# main.net
KiCad netlist of a schematic drawn in Altium Designer
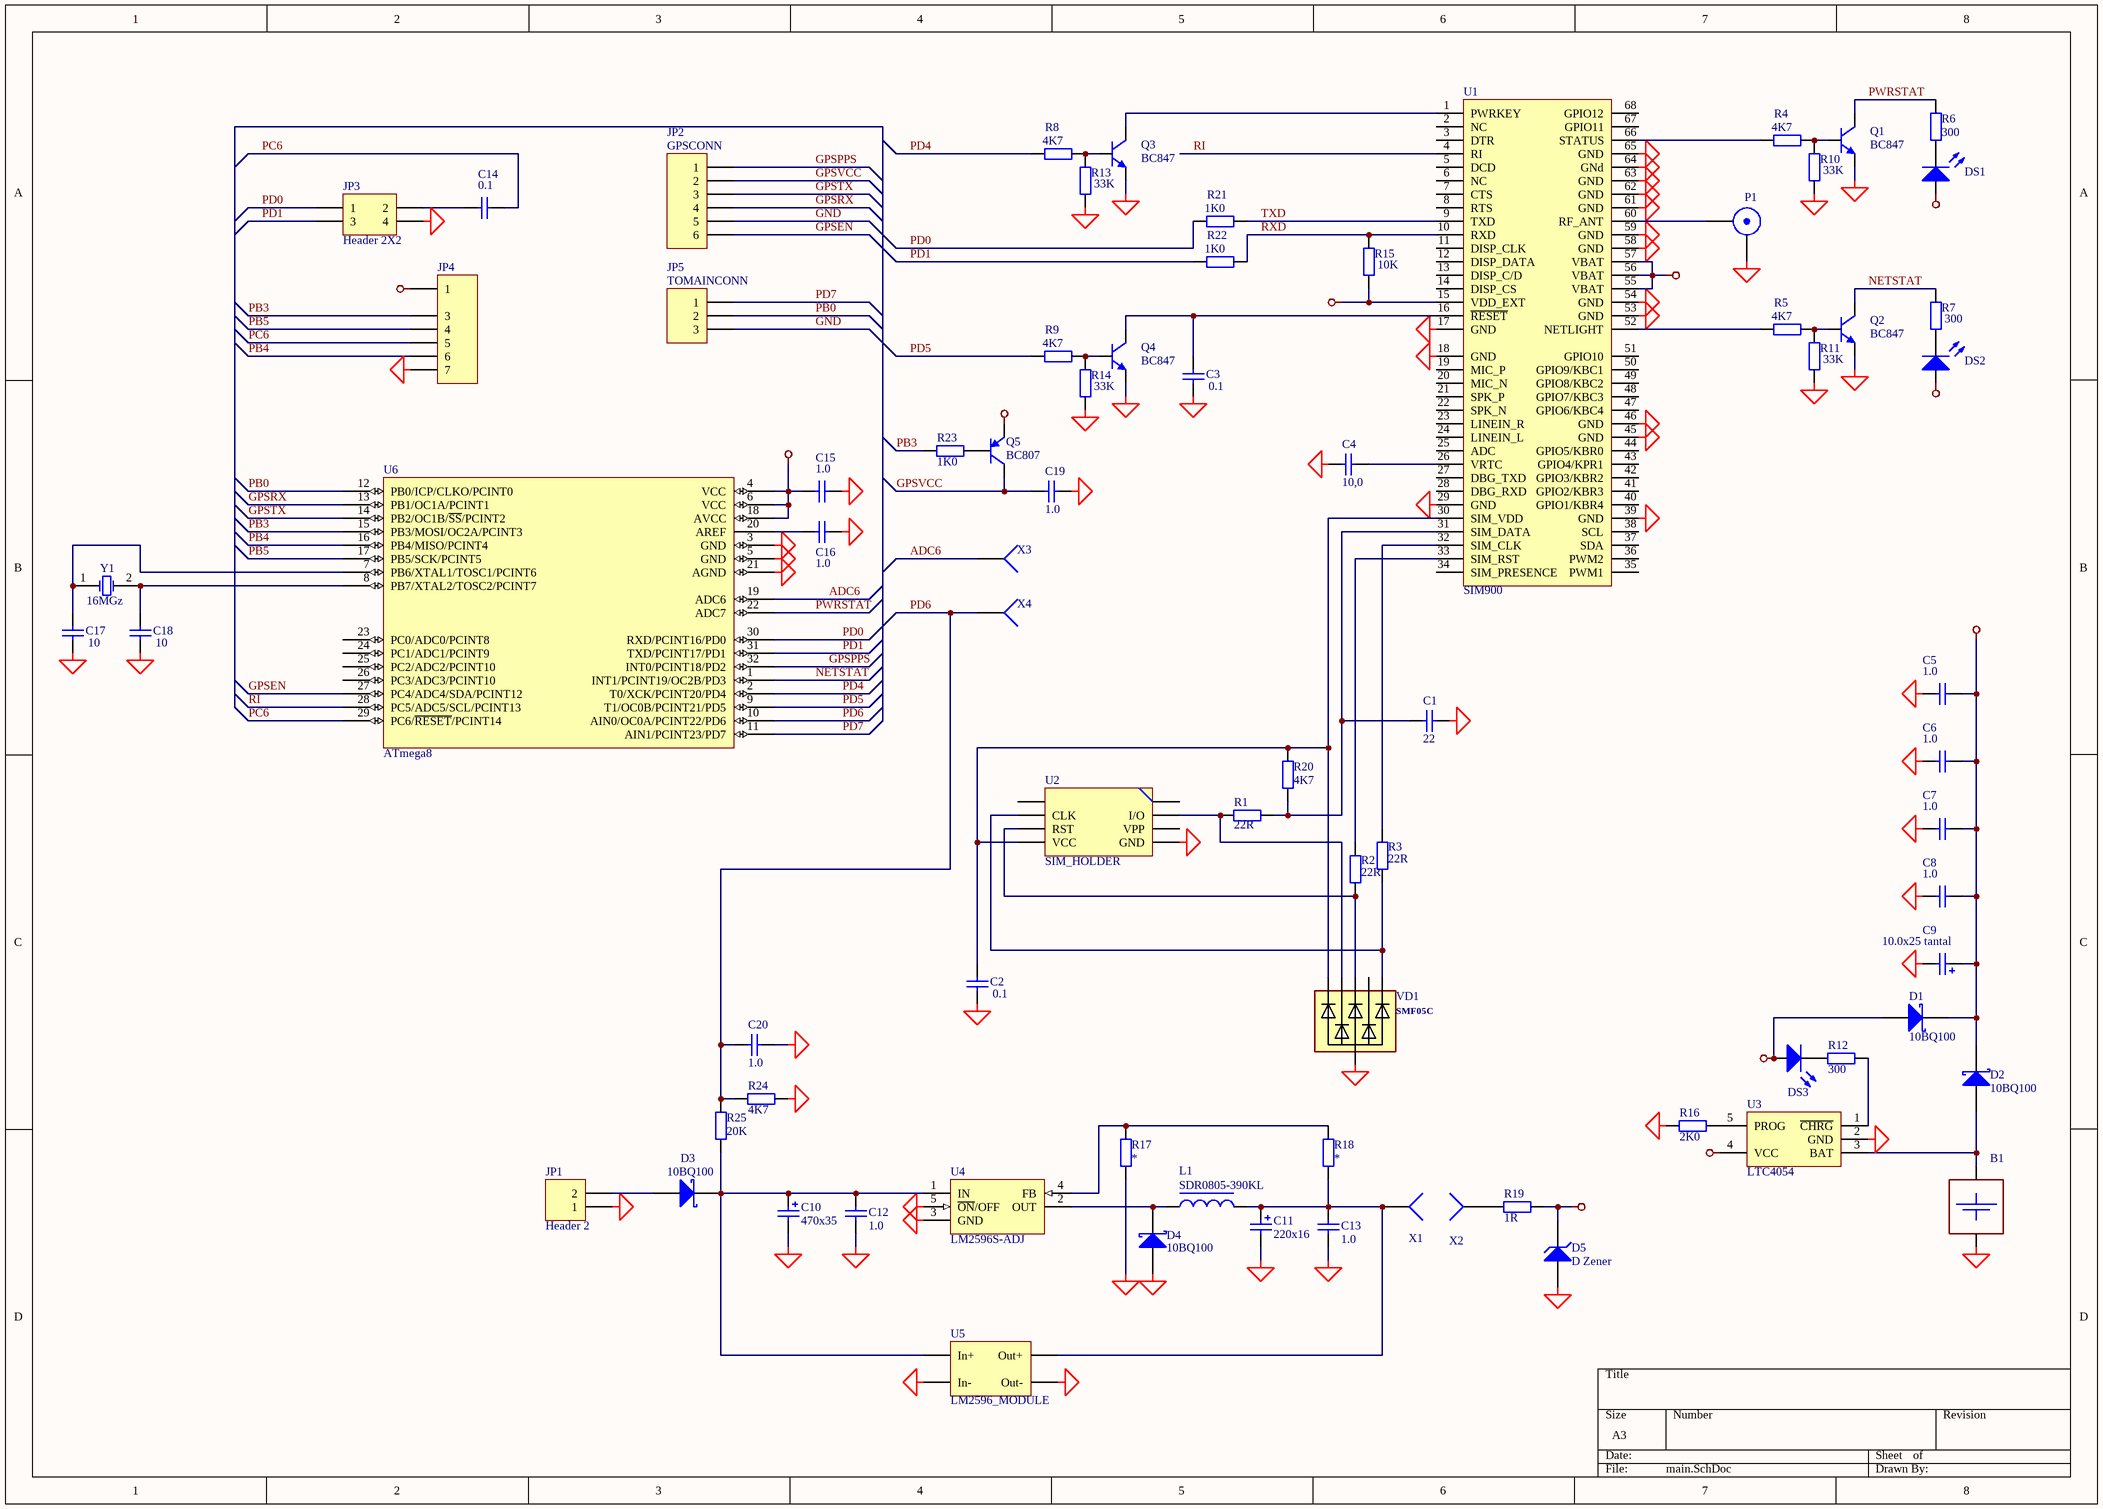
[diagram p0: main.SchDoc]

(export (version "E")
  (design (tool "Eeschema 10.0.6"))
  (components
    (comp (ref "B1")
      (value "BAT18650_HOLDER")
      (footprint "BAT18650_HOLDER")
      (libsource (lib "PAL") (part "BAT18650_HOLDER"))
    )
    (comp (ref "C1")
      (value "22")
      (footprint "_1206")
      (description "Capacitor")
      (fields (field (name "MANUFACTURER") "Generic Components") (field (name "PUBLISHER") "Altium Limited"))
      (libsource (lib "Miscellaneous Devices") (part "Cap Semi"))
    )
    (comp (ref "C2")
      (value "0.1")
      (footprint "_1206")
      (description "Capacitor")
      (fields (field (name "MANUFACTURER") "Generic Components") (field (name "PUBLISHER") "Altium Limited"))
      (libsource (lib "Miscellaneous Devices") (part "Cap Semi"))
    )
    (comp (ref "C3")
      (value "0.1")
      (footprint "_1206")
      (description "Capacitor")
      (fields (field (name "MANUFACTURER") "Generic Components") (field (name "PUBLISHER") "Altium Limited"))
      (libsource (lib "Miscellaneous Devices") (part "Cap Semi"))
    )
    (comp (ref "C4")
      (value "10,0")
      (footprint "_1206")
      (description "Capacitor")
      (fields (field (name "MANUFACTURER") "Generic Components") (field (name "PUBLISHER") "Altium Limited"))
      (libsource (lib "Miscellaneous Devices") (part "Cap Semi"))
    )
    (comp (ref "C5")
      (value "1.0")
      (footprint "_1206")
      (description "Capacitor")
      (fields (field (name "MANUFACTURER") "Generic Components") (field (name "PUBLISHER") "Altium Limited"))
      (libsource (lib "Miscellaneous Devices") (part "Cap Semi"))
    )
    (comp (ref "C6")
      (value "1.0")
      (footprint "_1206")
      (description "Capacitor")
      (fields (field (name "MANUFACTURER") "Generic Components") (field (name "PUBLISHER") "Altium Limited"))
      (libsource (lib "Miscellaneous Devices") (part "Cap Semi"))
    )
    (comp (ref "C7")
      (value "1.0")
      (footprint "_1206")
      (description "Capacitor")
      (fields (field (name "MANUFACTURER") "Generic Components") (field (name "PUBLISHER") "Altium Limited"))
      (libsource (lib "Miscellaneous Devices") (part "Cap Semi"))
    )
    (comp (ref "C8")
      (value "1.0")
      (footprint "_1206")
      (description "Capacitor")
      (fields (field (name "MANUFACTURER") "Generic Components") (field (name "PUBLISHER") "Altium Limited"))
      (libsource (lib "Miscellaneous Devices") (part "Cap Semi"))
    )
    (comp (ref "C9")
      (value "10.0x25 tantal")
      (footprint "CAP_EL_6_3")
      (description "Polarized Capacitor (Radial)")
      (fields (field (name "MANUFACTURER") "Generic Components") (field (name "PUBLISHER") "Altium Limited"))
      (libsource (lib "PAL") (part "Cap Pol1"))
    )
    (comp (ref "C10")
      (value "470x35")
      (footprint "el5")
      (description "Polarized Capacitor (Radial)")
      (fields (field (name "MANUFACTURER") "Generic Components") (field (name "PUBLISHER") "Altium Limited"))
      (libsource (lib "BUF") (part "Cap Pol"))
    )
    (comp (ref "C11")
      (value "220x16")
      (footprint "el3")
      (description "Polarized Capacitor (Radial)")
      (fields (field (name "MANUFACTURER") "Generic Components") (field (name "PUBLISHER") "Altium Limited"))
      (libsource (lib "BUF") (part "Cap Pol"))
    )
    (comp (ref "C12")
      (value "Cap")
      (footprint "_1206")
      (description "Capacitor")
      (fields
        (field (name "MANUFACTURER") "Generic Components")
        (field (name "ALTIUM_VALUE") "1.0")
        (field (name "PUBLISHER") "Altium Limited")
      )
      (libsource (lib "BUF") (part "Cap"))
    )
    (comp (ref "C13")
      (value "Cap")
      (footprint "_1206")
      (description "Capacitor")
      (fields
        (field (name "MANUFACTURER") "Generic Components")
        (field (name "ALTIUM_VALUE") "1.0")
        (field (name "PUBLISHER") "Altium Limited")
      )
      (libsource (lib "BUF") (part "Cap"))
    )
    (comp (ref "C14")
      (value "0.1")
      (footprint "_1206")
      (description "Capacitor")
      (fields (field (name "MANUFACTURER") "Generic Components") (field (name "PUBLISHER") "Altium Limited"))
      (libsource (lib "Miscellaneous Devices") (part "Cap Semi"))
    )
    (comp (ref "C15")
      (value "1.0")
      (footprint "_1206")
      (description "Capacitor")
      (fields (field (name "MANUFACTURER") "Generic Components") (field (name "PUBLISHER") "Altium Limited"))
      (libsource (lib "Miscellaneous Devices") (part "Cap Semi"))
    )
    (comp (ref "C16")
      (value "1.0")
      (footprint "_1206")
      (description "Capacitor")
      (fields (field (name "MANUFACTURER") "Generic Components") (field (name "PUBLISHER") "Altium Limited"))
      (libsource (lib "Miscellaneous Devices") (part "Cap Semi"))
    )
    (comp (ref "C17")
      (value "10")
      (footprint "_1206")
      (description "Capacitor")
      (fields (field (name "MANUFACTURER") "Generic Components") (field (name "PUBLISHER") "Altium Limited"))
      (libsource (lib "Miscellaneous Devices") (part "Cap Semi"))
    )
    (comp (ref "C18")
      (value "10")
      (footprint "_1206")
      (description "Capacitor")
      (fields (field (name "MANUFACTURER") "Generic Components") (field (name "PUBLISHER") "Altium Limited"))
      (libsource (lib "Miscellaneous Devices") (part "Cap Semi"))
    )
    (comp (ref "C19")
      (value "1.0")
      (footprint "_1206")
      (description "Capacitor")
      (fields (field (name "MANUFACTURER") "Generic Components") (field (name "PUBLISHER") "Altium Limited"))
      (libsource (lib "Miscellaneous Devices") (part "Cap Semi"))
    )
    (comp (ref "C20")
      (value "Cap")
      (footprint "_1206")
      (description "Capacitor")
      (fields
        (field (name "MANUFACTURER") "Generic Components")
        (field (name "ALTIUM_VALUE") "1.0")
        (field (name "PUBLISHER") "Altium Limited")
      )
      (libsource (lib "BUF") (part "Cap"))
    )
    (comp (ref "D1")
      (value "10BQ100")
      (footprint "DSO-C2/X2.3")
      (description "Schottky Rectifier")
      (fields
        (field (name "MANUFACTURER") "International Rectifier")
        (field (name "PUBLISHER") "Altium Limited")
      )
      (libsource (lib "IR Discrete Diode") (part "10BQ015"))
    )
    (comp (ref "D2")
      (value "10BQ100")
      (footprint "DSO-C2/X2.3")
      (description "Schottky Rectifier")
      (fields
        (field (name "MANUFACTURER") "International Rectifier")
        (field (name "PUBLISHER") "Altium Limited")
      )
      (libsource (lib "IR Discrete Diode") (part "10BQ015"))
    )
    (comp (ref "D3")
      (value "10BQ100")
      (footprint "DSO-C2/X2.3")
      (description "Schottky Rectifier")
      (fields
        (field (name "MANUFACTURER") "International Rectifier")
        (field (name "PUBLISHER") "Altium Limited")
      )
      (libsource (lib "IR Discrete Diode") (part "10BQ015"))
    )
    (comp (ref "D4")
      (value "10BQ100")
      (footprint "DSO-C2/X2.3")
      (description "Schottky Rectifier")
      (fields
        (field (name "MANUFACTURER") "International Rectifier")
        (field (name "PUBLISHER") "Altium Limited")
      )
      (libsource (lib "IR Discrete Diode") (part "10BQ015"))
    )
    (comp (ref "D5")
      (value "D Zener")
      (footprint "_1206d")
      (description "Zener Diode")
      (fields (field (name "MANUFACTURER") "Generic Components") (field (name "PUBLISHER") "Altium Limited"))
      (libsource (lib "Miscellaneous Devices") (part "D Zener"))
    )
    (comp (ref "DS1")
      (value "LED0")
      (footprint "el3")
      (description "Typical INFRARED GaAs LED")
      (fields (field (name "MANUFACTURER") "Generic Components") (field (name "PUBLISHER") "Altium Limited"))
      (libsource (lib "PAL") (part "LED0"))
    )
    (comp (ref "DS2")
      (value "LED0")
      (footprint "el3")
      (description "Typical INFRARED GaAs LED")
      (fields (field (name "MANUFACTURER") "Generic Components") (field (name "PUBLISHER") "Altium Limited"))
      (libsource (lib "PAL") (part "LED0"))
    )
    (comp (ref "DS3")
      (value "LED0")
      (footprint "el3")
      (description "Typical INFRARED GaAs LED")
      (fields (field (name "MANUFACTURER") "Generic Components") (field (name "PUBLISHER") "Altium Limited"))
      (libsource (lib "") (part "LED0_1"))
    )
    (comp (ref "JP1")
      (value "Header 2")
      (footprint "BT5-2")
      (description "Header, 2-Pin")
      (fields (field (name "MANUFACTURER") "Generic Components") (field (name "PUBLISHER") "Altium Limited"))
      (libsource (lib "BUF") (part "Header 2"))
    )
    (comp (ref "JP2")
      (value "GPSCONN")
      (footprint "HDR1X6")
      (description "Header, 6-Pin")
      (fields (field (name "MANUFACTURER") "Generic Components") (field (name "PUBLISHER") "Altium Limited"))
      (libsource (lib "Miscellaneous Connectors") (part "Header 6"))
    )
    (comp (ref "JP3")
      (value "Header 2X2")
      (footprint "HDR2X2")
      (description "Header, 2-Pin, Dual row")
      (fields (field (name "MANUFACTURER") "Generic Components") (field (name "PUBLISHER") "Altium Limited"))
      (libsource (lib "Miscellaneous Connectors") (part "Header 2X2"))
    )
    (comp (ref "JP4")
      (value "AVR_conn")
      (footprint "AVR_CONN")
      (description "Header, 7-Pin")
      (fields (field (name "MANUFACTURER") "Generic Components") (field (name "PUBLISHER") "Altium Limited"))
      (libsource (lib "PAL") (part "AVR_conn"))
    )
    (comp (ref "JP5")
      (value "TOMAINCONN")
      (footprint "HDR1X3")
      (description "Header, 3-Pin")
      (fields (field (name "MANUFACTURER") "Generic Components") (field (name "PUBLISHER") "Altium Limited"))
      (libsource (lib "Miscellaneous Connectors") (part "Header 3"))
    )
    (comp (ref "L1")
      (value "SDR0805-390KL")
      (footprint "L10x10")
      (description "Magnetic-Core Inductor")
      (fields (field (name "MANUFACTURER") "Generic Components") (field (name "PUBLISHER") "Altium Limited"))
      (libsource (lib "PAL") (part "Inductor Konstr 2"))
    )
    (comp (ref "P1")
      (value "SMB")
      (footprint "SMB_V-RJ45")
      (description "SMB Straight Connector")
      (fields (field (name "MANUFACTURER") "Generic Components") (field (name "PUBLISHER") "Altium Limited"))
      (libsource (lib "Miscellaneous Connectors") (part "SMB"))
    )
    (comp (ref "Q1")
      (value "BC847")
      (footprint "SO-G3/C2.5")
      (description "General Purpose Transistor NPN Silicon")
      (fields (field (name "MANUFACTURER") "Motorola") (field (name "PUBLISHER") "Altium Limited"))
      (libsource (lib "PAL") (part "BC847ALT1"))
    )
    (comp (ref "Q2")
      (value "BC847")
      (footprint "SO-G3/C2.5")
      (description "General Purpose Transistor NPN Silicon")
      (fields (field (name "MANUFACTURER") "Motorola") (field (name "PUBLISHER") "Altium Limited"))
      (libsource (lib "PAL") (part "BC847ALT1"))
    )
    (comp (ref "Q3")
      (value "BC847")
      (footprint "SO-G3/C2.5")
      (description "General Purpose Transistor NPN Silicon")
      (fields (field (name "MANUFACTURER") "Motorola") (field (name "PUBLISHER") "Altium Limited"))
      (libsource (lib "PAL") (part "BC847ALT1"))
    )
    (comp (ref "Q4")
      (value "BC847")
      (footprint "SO-G3/C2.5")
      (description "General Purpose Transistor NPN Silicon")
      (fields (field (name "MANUFACTURER") "Motorola") (field (name "PUBLISHER") "Altium Limited"))
      (libsource (lib "PAL") (part "BC847ALT1"))
    )
    (comp (ref "Q5")
      (value "BC807")
      (footprint "SO-G3/C2.5")
      (description "General Purpose Transistor PNP Silicon")
      (fields (field (name "MANUFACTURER") "Motorola") (field (name "PUBLISHER") "Altium Limited"))
      (libsource (lib "PAL") (part "BC857ALT1"))
    )
    (comp (ref "R1")
      (value "22R")
      (footprint "_1206")
      (description "Resistor")
      (fields (field (name "MANUFACTURER") "Generic Components") (field (name "PUBLISHER") "Altium Limited"))
      (libsource (lib "") (part "Res2_1"))
    )
    (comp (ref "R2")
      (value "22R")
      (footprint "_1206")
      (description "Resistor")
      (fields (field (name "MANUFACTURER") "Generic Components") (field (name "PUBLISHER") "Altium Limited"))
      (libsource (lib "Miscellaneous Devices") (part "Res2"))
    )
    (comp (ref "R3")
      (value "22R")
      (footprint "_1206")
      (description "Resistor")
      (fields (field (name "MANUFACTURER") "Generic Components") (field (name "PUBLISHER") "Altium Limited"))
      (libsource (lib "Miscellaneous Devices") (part "Res2"))
    )
    (comp (ref "R4")
      (value "4K7")
      (footprint "_1206")
      (description "Resistor")
      (fields (field (name "MANUFACTURER") "Generic Components") (field (name "PUBLISHER") "Altium Limited"))
      (libsource (lib "Miscellaneous Devices") (part "Res2"))
    )
    (comp (ref "R5")
      (value "4K7")
      (footprint "_1206")
      (description "Resistor")
      (fields (field (name "MANUFACTURER") "Generic Components") (field (name "PUBLISHER") "Altium Limited"))
      (libsource (lib "Miscellaneous Devices") (part "Res2"))
    )
    (comp (ref "R6")
      (value "300")
      (footprint "_1206")
      (description "Resistor")
      (fields (field (name "MANUFACTURER") "Generic Components") (field (name "PUBLISHER") "Altium Limited"))
      (libsource (lib "") (part "Res2_2"))
    )
    (comp (ref "R7")
      (value "300")
      (footprint "_1206")
      (description "Resistor")
      (fields (field (name "MANUFACTURER") "Generic Components") (field (name "PUBLISHER") "Altium Limited"))
      (libsource (lib "") (part "Res2_1"))
    )
    (comp (ref "R8")
      (value "4K7")
      (footprint "_1206")
      (description "Resistor")
      (fields (field (name "MANUFACTURER") "Generic Components") (field (name "PUBLISHER") "Altium Limited"))
      (libsource (lib "Miscellaneous Devices") (part "Res2"))
    )
    (comp (ref "R9")
      (value "4K7")
      (footprint "_1206")
      (description "Resistor")
      (fields (field (name "MANUFACTURER") "Generic Components") (field (name "PUBLISHER") "Altium Limited"))
      (libsource (lib "Miscellaneous Devices") (part "Res2"))
    )
    (comp (ref "R10")
      (value "33K")
      (footprint "_1206")
      (description "Resistor")
      (fields (field (name "MANUFACTURER") "Generic Components") (field (name "PUBLISHER") "Altium Limited"))
      (libsource (lib "") (part "Res2_1"))
    )
    (comp (ref "R11")
      (value "33K")
      (footprint "_1206")
      (description "Resistor")
      (fields (field (name "MANUFACTURER") "Generic Components") (field (name "PUBLISHER") "Altium Limited"))
      (libsource (lib "") (part "Res2_1"))
    )
    (comp (ref "R12")
      (value "300")
      (footprint "_1206")
      (description "Resistor")
      (fields (field (name "MANUFACTURER") "Generic Components") (field (name "PUBLISHER") "Altium Limited"))
      (libsource (lib "") (part "Res2_3"))
    )
    (comp (ref "R13")
      (value "33K")
      (footprint "_1206")
      (description "Resistor")
      (fields (field (name "MANUFACTURER") "Generic Components") (field (name "PUBLISHER") "Altium Limited"))
      (libsource (lib "") (part "Res2_1"))
    )
    (comp (ref "R14")
      (value "33K")
      (footprint "_1206")
      (description "Resistor")
      (fields (field (name "MANUFACTURER") "Generic Components") (field (name "PUBLISHER") "Altium Limited"))
      (libsource (lib "") (part "Res2_1"))
    )
    (comp (ref "R15")
      (value "10K")
      (footprint "_1206")
      (description "Resistor")
      (fields (field (name "MANUFACTURER") "Generic Components") (field (name "PUBLISHER") "Altium Limited"))
      (libsource (lib "") (part "Res2_1"))
    )
    (comp (ref "R16")
      (value "2K0")
      (footprint "_1206")
      (description "Resistor")
      (fields (field (name "MANUFACTURER") "Generic Components") (field (name "PUBLISHER") "Altium Limited"))
      (libsource (lib "") (part "Res2_3"))
    )
    (comp (ref "R17")
      (value "*")
      (footprint "_1206")
      (description "Resistor")
      (fields (field (name "MANUFACTURER") "Generic Components") (field (name "PUBLISHER") "Altium Limited"))
      (libsource (lib "Miscellaneous Devices") (part "Res2"))
    )
    (comp (ref "R18")
      (value "*")
      (footprint "_1206")
      (description "Resistor")
      (fields (field (name "MANUFACTURER") "Generic Components") (field (name "PUBLISHER") "Altium Limited"))
      (libsource (lib "Miscellaneous Devices") (part "Res2"))
    )
    (comp (ref "R19")
      (value "1R")
      (footprint "_1206")
      (description "Resistor")
      (fields (field (name "MANUFACTURER") "Generic Components") (field (name "PUBLISHER") "Altium Limited"))
      (libsource (lib "") (part "Res2_2"))
    )
    (comp (ref "R20")
      (value "4K7")
      (footprint "_1206")
      (description "Resistor")
      (fields (field (name "MANUFACTURER") "Generic Components") (field (name "PUBLISHER") "Altium Limited"))
      (libsource (lib "Miscellaneous Devices") (part "Res2"))
    )
    (comp (ref "R21")
      (value "1K0")
      (footprint "_1206")
      (description "Resistor")
      (fields (field (name "MANUFACTURER") "Generic Components") (field (name "PUBLISHER") "Altium Limited"))
      (libsource (lib "Miscellaneous Devices") (part "Res2"))
    )
    (comp (ref "R22")
      (value "1K0")
      (footprint "_1206")
      (description "Resistor")
      (fields (field (name "MANUFACTURER") "Generic Components") (field (name "PUBLISHER") "Altium Limited"))
      (libsource (lib "Miscellaneous Devices") (part "Res2"))
    )
    (comp (ref "R23")
      (value "Res2")
      (footprint "_1206")
      (description "Resistor")
      (fields
        (field (name "MANUFACTURER") "Generic Components")
        (field (name "ALTIUM_VALUE") "1K0")
        (field (name "PUBLISHER") "Altium Limited")
      )
      (libsource (lib "Miscellaneous Devices") (part "Res2"))
    )
    (comp (ref "R24")
      (value "4K7")
      (footprint "_1206")
      (description "Resistor")
      (fields (field (name "MANUFACTURER") "Generic Components") (field (name "PUBLISHER") "Altium Limited"))
      (libsource (lib "") (part "Res2_2"))
    )
    (comp (ref "R25")
      (value "20K")
      (footprint "_1206")
      (description "Resistor")
      (fields (field (name "MANUFACTURER") "Generic Components") (field (name "PUBLISHER") "Altium Limited"))
      (libsource (lib "Miscellaneous Devices") (part "Res2"))
    )
    (comp (ref "U1") (value "SIM900") (footprint "SIM900F") (libsource (lib "Schlib1") (part "SIM900")))
    (comp (ref "U2")
      (value "SIM_HOLDER")
      (footprint "SIM_HOLDER_1")
      (libsource (lib "Schlib1") (part "SIM_HOLDER"))
    )
    (comp (ref "U3") (value "LTC4054") (footprint "SO-G5/P.95") (libsource (lib "PAL") (part "LTC4054")))
    (comp (ref "U4")
      (value "LM2596S-ADJ")
      (footprint "SIP-G5/Y2.1")
      (description "Simple Switcher Power Converter 150 kHz 3A Step Down Voltage Regulator")
      (fields
        (field (name "MANUFACTURER") "National Semiconductor")
        (field (name "PUBLISHER") "Altium Limited")
      )
      (libsource (lib "NSC Power Mgt Switching Regulator") (part "LM2596S-ADJ"))
    )
    (comp (ref "U5")
      (value "LM2596_MODULE")
      (footprint "LM2596_MODULE_1")
      (libsource (lib "PAL") (part "LM2596_MODULE"))
    )
    (comp (ref "U6")
      (value "ATmega8")
      (footprint "QFP7X7-G32/X.5N")
      (libsource (lib "PAL") (part "ATmega48/TQFP"))
    )
    (comp (ref "VD1")
      (value "*")
      (footprint "sot363")
      (fields (field (name "MANUFACTURERPARTNUMBER") "SMF05C"))
      (libsource (lib "PAL") (part "SMF05C"))
    )
    (comp (ref "X1")
      (value "Socket")
      (footprint "PIN1")
      (fields (field (name "MANUFACTURER") "Generic Components") (field (name "PUBLISHER") "Altium Limited"))
      (libsource (lib "Miscellaneous Connectors") (part "Socket"))
    )
    (comp (ref "X2")
      (value "Socket")
      (footprint "PIN1")
      (fields (field (name "MANUFACTURER") "Generic Components") (field (name "PUBLISHER") "Altium Limited"))
      (libsource (lib "Miscellaneous Connectors") (part "Socket"))
    )
    (comp (ref "X3")
      (value "Socket")
      (footprint "PIN1")
      (fields (field (name "MANUFACTURER") "Generic Components") (field (name "PUBLISHER") "Altium Limited"))
      (libsource (lib "Miscellaneous Connectors") (part "Socket"))
    )
    (comp (ref "X4")
      (value "Socket")
      (footprint "PIN1")
      (fields (field (name "MANUFACTURER") "Generic Components") (field (name "PUBLISHER") "Altium Limited"))
      (libsource (lib "Miscellaneous Connectors") (part "Socket"))
    )
    (comp (ref "Y1")
      (value "16MGz")
      (footprint "qwarz1")
      (description "Crystal Oscillator")
      (fields (field (name "MANUFACTURER") "Generic Components") (field (name "PUBLISHER") "Altium Limited"))
      (libsource (lib "Miscellaneous Devices") (part "XTAL"))
    )
  )
  (nets
    (net (code "1") (name "+5v") (class "Default")
      (node (ref "D1") (pin "1") (pinfunction "A_1") (pintype "passive"))
      (node (ref "D5") (pin "2") (pinfunction "K_2") (pintype "passive"))
      (node (ref "DS3") (pin "1") (pinfunction "A_1") (pintype "passive"))
      (node (ref "R19") (pin "2") (pinfunction "2_2") (pintype "passive"))
      (node (ref "U3") (pin "4") (pinfunction "VCC_4") (pintype "passive"))
    )
    (net (code "2") (name "/ADC6") (class "Default")
      (node (ref "U6") (pin "19") (pinfunction "ADC6_19") (pintype "bidirectional"))
      (node (ref "X3") (pin "1") (pinfunction "1_1") (pintype "passive"))
    )
    (net (code "3") (name "/GPSEN") (class "Default")
      (node (ref "JP2") (pin "6") (pinfunction "6_6") (pintype "passive"))
      (node (ref "U6") (pin "27") (pinfunction "PC4/ADC4/SDA/PCINT12_27") (pintype "bidirectional"))
    )
    (net (code "4") (name "/GPSPPS") (class "Default")
      (node (ref "JP2") (pin "1") (pinfunction "1_1") (pintype "passive"))
      (node (ref "U6") (pin "32") (pinfunction "INT0/PCINT18/PD2_32") (pintype "bidirectional"))
    )
    (net (code "5") (name "/GPSRX") (class "Default")
      (node (ref "JP2") (pin "4") (pinfunction "4_4") (pintype "passive"))
      (node (ref "U6") (pin "13") (pinfunction "PB1/OC1A/PCINT1_13") (pintype "bidirectional"))
    )
    (net (code "6") (name "/GPSTX") (class "Default")
      (node (ref "JP2") (pin "3") (pinfunction "3_3") (pintype "passive"))
      (node (ref "U6") (pin "14") (pinfunction "PB2/OC1B/~{SS}/PCINT2_14") (pintype "bidirectional"))
    )
    (net (code "7") (name "/GPSVCC") (class "Default")
      (node (ref "C19") (pin "2") (pinfunction "2_2") (pintype "passive"))
      (node (ref "JP2") (pin "2") (pinfunction "2_2") (pintype "passive"))
      (node (ref "Q5") (pin "3") (pinfunction "C_3") (pintype "passive"))
    )
    (net (code "8") (name "/NETSTAT") (class "Default")
      (node (ref "Q2") (pin "3") (pinfunction "C_3") (pintype "passive"))
      (node (ref "R7") (pin "1") (pinfunction "1_1") (pintype "passive"))
      (node (ref "U6") (pin "1") (pinfunction "INT1/PCINT19/OC2B/PD3_1") (pintype "bidirectional"))
    )
    (net (code "9") (name "/PB0") (class "Default")
      (node (ref "JP5") (pin "2") (pinfunction "2_2") (pintype "passive"))
      (node (ref "U6") (pin "12") (pinfunction "PB0/ICP/CLKO/PCINT0_12") (pintype "bidirectional"))
    )
    (net (code "10") (name "/PB3") (class "Default")
      (node (ref "JP4") (pin "3") (pinfunction "3_3") (pintype "passive"))
      (node (ref "R23") (pin "2") (pinfunction "2_2") (pintype "passive"))
      (node (ref "U6") (pin "15") (pinfunction "PB3/MOSI/OC2A/PCINT3_15") (pintype "bidirectional"))
    )
    (net (code "11") (name "/PB4") (class "Default")
      (node (ref "JP4") (pin "6") (pinfunction "6_6") (pintype "passive"))
      (node (ref "U6") (pin "16") (pinfunction "PB4/MISO/PCINT4_16") (pintype "bidirectional"))
    )
    (net (code "12") (name "/PB5") (class "Default")
      (node (ref "JP4") (pin "4") (pinfunction "4_4") (pintype "passive"))
      (node (ref "U6") (pin "17") (pinfunction "PB5/SCK/PCINT5_17") (pintype "bidirectional"))
    )
    (net (code "13") (name "/PC6") (class "Default")
      (node (ref "C14") (pin "1") (pinfunction "1_1") (pintype "passive"))
      (node (ref "JP4") (pin "5") (pinfunction "5_5") (pintype "passive"))
      (node (ref "U6") (pin "29") (pinfunction "PC6/~{RESET}/PCINT14_29") (pintype "bidirectional"))
    )
    (net (code "14") (name "/PD0") (class "Default")
      (node (ref "JP3") (pin "1") (pinfunction "1_1") (pintype "passive"))
      (node (ref "R21") (pin "2") (pinfunction "2_2") (pintype "passive"))
      (node (ref "U6") (pin "30") (pinfunction "RXD/PCINT16/PD0_30") (pintype "bidirectional"))
    )
    (net (code "15") (name "/PD1") (class "Default")
      (node (ref "JP3") (pin "3") (pinfunction "3_3") (pintype "passive"))
      (node (ref "R22") (pin "2") (pinfunction "2_2") (pintype "passive"))
      (node (ref "U6") (pin "31") (pinfunction "TXD/PCINT17/PD1_31") (pintype "bidirectional"))
    )
    (net (code "16") (name "/PD4") (class "Default")
      (node (ref "R8") (pin "2") (pinfunction "2_2") (pintype "passive"))
      (node (ref "U6") (pin "2") (pinfunction "T0/XCK/PCINT20/PD4_2") (pintype "bidirectional"))
    )
    (net (code "17") (name "/PD5") (class "Default")
      (node (ref "R9") (pin "2") (pinfunction "2_2") (pintype "passive"))
      (node (ref "U6") (pin "9") (pinfunction "T1/OC0B/PCINT21/PD5_9") (pintype "bidirectional"))
    )
    (net (code "18") (name "/PD6") (class "Default")
      (node (ref "C20") (pin "2") (pinfunction "2_2") (pintype "passive"))
      (node (ref "R24") (pin "1") (pinfunction "1_1") (pintype "passive"))
      (node (ref "R25") (pin "1") (pinfunction "1_1") (pintype "passive"))
      (node (ref "U6") (pin "10") (pinfunction "AIN0/OC0A/PCINT22/PD6_10") (pintype "bidirectional"))
      (node (ref "X4") (pin "1") (pinfunction "1_1") (pintype "passive"))
    )
    (net (code "19") (name "/PD7") (class "Default")
      (node (ref "JP5") (pin "1") (pinfunction "1_1") (pintype "passive"))
      (node (ref "U6") (pin "11") (pinfunction "AIN1/PCINT23/PD7_11") (pintype "bidirectional"))
    )
    (net (code "20") (name "/PWRSTAT") (class "Default")
      (node (ref "Q1") (pin "3") (pinfunction "C_3") (pintype "passive"))
      (node (ref "R6") (pin "2") (pinfunction "2_2") (pintype "passive"))
      (node (ref "U6") (pin "22") (pinfunction "ADC7_22") (pintype "bidirectional"))
    )
    (net (code "21") (name "/RI") (class "Default")
      (node (ref "U1") (pin "4") (pinfunction "RI_4") (pintype "passive"))
      (node (ref "U6") (pin "28") (pinfunction "PC5/ADC5/SCL/PCINT13_28") (pintype "bidirectional"))
    )
    (net (code "22") (name "/RXD") (class "Default")
      (node (ref "R15") (pin "1") (pinfunction "1_1") (pintype "passive"))
      (node (ref "R22") (pin "1") (pinfunction "1_1") (pintype "passive"))
      (node (ref "U1") (pin "10") (pinfunction "RXD_10") (pintype "passive"))
    )
    (net (code "23") (name "/TXD") (class "Default")
      (node (ref "R21") (pin "1") (pinfunction "1_1") (pintype "passive"))
      (node (ref "U1") (pin "9") (pinfunction "TXD_9") (pintype "passive"))
    )
    (net (code "24") (name "GND") (class "Default")
      (node (ref "B1") (pin "2") (pinfunction "-_2") (pintype "passive"))
      (node (ref "C1") (pin "1") (pinfunction "1_1") (pintype "passive"))
      (node (ref "C10") (pin "2") (pinfunction "2_2") (pintype "passive"))
      (node (ref "C11") (pin "2") (pinfunction "2_2") (pintype "passive"))
      (node (ref "C12") (pin "1") (pinfunction "1_1") (pintype "passive"))
      (node (ref "C13") (pin "1") (pinfunction "1_1") (pintype "passive"))
      (node (ref "C15") (pin "1") (pinfunction "1_1") (pintype "passive"))
      (node (ref "C16") (pin "1") (pinfunction "1_1") (pintype "passive"))
      (node (ref "C17") (pin "1") (pinfunction "1_1") (pintype "passive"))
      (node (ref "C18") (pin "1") (pinfunction "1_1") (pintype "passive"))
      (node (ref "C19") (pin "1") (pinfunction "1_1") (pintype "passive"))
      (node (ref "C2") (pin "1") (pinfunction "1_1") (pintype "passive"))
      (node (ref "C20") (pin "1") (pinfunction "1_1") (pintype "passive"))
      (node (ref "C3") (pin "1") (pinfunction "1_1") (pintype "passive"))
      (node (ref "C4") (pin "2") (pinfunction "2_2") (pintype "passive"))
      (node (ref "C5") (pin "1") (pinfunction "1_1") (pintype "passive"))
      (node (ref "C6") (pin "1") (pinfunction "1_1") (pintype "passive"))
      (node (ref "C7") (pin "1") (pinfunction "1_1") (pintype "passive"))
      (node (ref "C8") (pin "1") (pinfunction "1_1") (pintype "passive"))
      (node (ref "C9") (pin "2") (pinfunction "2_2") (pintype "passive"))
      (node (ref "D4") (pin "1") (pinfunction "A_1") (pintype "passive"))
      (node (ref "D5") (pin "1") (pinfunction "A_1") (pintype "passive"))
      (node (ref "JP1") (pin "1") (pinfunction "1_1") (pintype "passive"))
      (node (ref "JP2") (pin "5") (pinfunction "5_5") (pintype "passive"))
      (node (ref "JP3") (pin "4") (pinfunction "4_4") (pintype "passive"))
      (node (ref "JP4") (pin "7") (pinfunction "7_7") (pintype "passive"))
      (node (ref "JP5") (pin "3") (pinfunction "3_3") (pintype "passive"))
      (node (ref "P1") (pin "2") (pinfunction "Y_2") (pintype "passive"))
      (node (ref "Q1") (pin "2") (pinfunction "E_2") (pintype "passive"))
      (node (ref "Q2") (pin "2") (pinfunction "E_2") (pintype "passive"))
      (node (ref "Q3") (pin "2") (pinfunction "E_2") (pintype "passive"))
      (node (ref "Q4") (pin "2") (pinfunction "E_2") (pintype "passive"))
      (node (ref "R10") (pin "2") (pinfunction "2_2") (pintype "passive"))
      (node (ref "R11") (pin "2") (pinfunction "2_2") (pintype "passive"))
      (node (ref "R13") (pin "2") (pinfunction "2_2") (pintype "passive"))
      (node (ref "R14") (pin "2") (pinfunction "2_2") (pintype "passive"))
      (node (ref "R16") (pin "2") (pinfunction "2_2") (pintype "passive"))
      (node (ref "R17") (pin "2") (pinfunction "2_2") (pintype "passive"))
      (node (ref "R24") (pin "2") (pinfunction "2_2") (pintype "passive"))
      (node (ref "U1") (pin "17") (pinfunction "GND_17") (pintype "passive"))
      (node (ref "U1") (pin "18") (pinfunction "GND_18") (pintype "passive"))
      (node (ref "U1") (pin "29") (pinfunction "GND_29") (pintype "passive"))
      (node (ref "U1") (pin "39") (pinfunction "GND_39") (pintype "passive"))
      (node (ref "U1") (pin "45") (pinfunction "GND_45") (pintype "passive"))
      (node (ref "U1") (pin "46") (pinfunction "GND_46") (pintype "passive"))
      (node (ref "U1") (pin "53") (pinfunction "GND_53") (pintype "passive"))
      (node (ref "U1") (pin "54") (pinfunction "GND_54") (pintype "passive"))
      (node (ref "U1") (pin "58") (pinfunction "GND_58") (pintype "passive"))
      (node (ref "U1") (pin "59") (pinfunction "GND_59") (pintype "passive"))
      (node (ref "U1") (pin "61") (pinfunction "GND_61") (pintype "passive"))
      (node (ref "U1") (pin "62") (pinfunction "GND_62") (pintype "passive"))
      (node (ref "U1") (pin "63") (pinfunction "GND_63") (pintype "passive"))
      (node (ref "U1") (pin "64") (pinfunction "GNd_64") (pintype "passive"))
      (node (ref "U1") (pin "65") (pinfunction "GND_65") (pintype "passive"))
      (node (ref "U2") (pin "5") (pinfunction "GND_5") (pintype "passive"))
      (node (ref "U3") (pin "2") (pinfunction "GND_2") (pintype "passive"))
      (node (ref "U4") (pin "3") (pinfunction "GND_3") (pintype "power_in"))
      (node (ref "U4") (pin "5") (pinfunction "~{ON}/OFF_5") (pintype "input"))
      (node (ref "U5") (pin "2") (pinfunction "In-_2") (pintype "passive"))
      (node (ref "U5") (pin "3") (pinfunction "Out-_3") (pintype "passive"))
      (node (ref "U6") (pin "21") (pinfunction "AGND_21") (pintype "bidirectional"))
      (node (ref "U6") (pin "3") (pinfunction "GND_3") (pintype "bidirectional"))
      (node (ref "U6") (pin "5") (pinfunction "GND_5") (pintype "bidirectional"))
      (node (ref "VD1") (pin "2") (pinfunction "2_2") (pintype "passive"))
    )
    (net (code "25") (name "Net-(B1-+)") (class "Default")
      (node (ref "B1") (pin "1") (pinfunction "+_1") (pintype "passive"))
      (node (ref "D2") (pin "1") (pinfunction "A_1") (pintype "passive"))
      (node (ref "U3") (pin "3") (pinfunction "BAT_3") (pintype "passive"))
    )
    (net (code "26") (name "Net-(C14-Pad2)") (class "Default")
      (node (ref "C14") (pin "2") (pinfunction "2_2") (pintype "passive"))
      (node (ref "JP3") (pin "2") (pinfunction "2_2") (pintype "passive"))
    )
    (net (code "27") (name "Net-(D3-A)") (class "Default")
      (node (ref "D3") (pin "1") (pinfunction "A_1") (pintype "passive"))
      (node (ref "JP1") (pin "2") (pinfunction "2_2") (pintype "passive"))
    )
    (net (code "28") (name "Net-(D3-K)") (class "Default")
      (node (ref "C10") (pin "1") (pinfunction "1_1") (pintype "passive"))
      (node (ref "C12") (pin "2") (pinfunction "2_2") (pintype "passive"))
      (node (ref "D3") (pin "2") (pinfunction "K_2") (pintype "passive"))
      (node (ref "R25") (pin "2") (pinfunction "2_2") (pintype "passive"))
      (node (ref "U4") (pin "1") (pinfunction "IN_1") (pintype "power_in"))
      (node (ref "U5") (pin "1") (pinfunction "In+_1") (pintype "passive"))
    )
    (net (code "29") (name "Net-(D4-K)") (class "Default")
      (node (ref "D4") (pin "2") (pinfunction "K_2") (pintype "passive"))
      (node (ref "L1") (pin "1") (pinfunction "1_1") (pintype "passive"))
      (node (ref "U4") (pin "2") (pinfunction "OUT_2") (pintype "power_in"))
    )
    (net (code "30") (name "Net-(DS1-K)") (class "Default")
      (node (ref "DS1") (pin "2") (pinfunction "K_2") (pintype "passive"))
      (node (ref "R6") (pin "1") (pinfunction "1_1") (pintype "passive"))
    )
    (net (code "31") (name "Net-(DS2-K)") (class "Default")
      (node (ref "DS2") (pin "2") (pinfunction "K_2") (pintype "passive"))
      (node (ref "R7") (pin "2") (pinfunction "2_2") (pintype "passive"))
    )
    (net (code "32") (name "Net-(DS3-K)") (class "Default")
      (node (ref "DS3") (pin "2") (pinfunction "K_2") (pintype "passive"))
      (node (ref "R12") (pin "2") (pinfunction "2_2") (pintype "passive"))
    )
    (net (code "33") (name "Net-(P1-X)") (class "Default")
      (node (ref "P1") (pin "1") (pinfunction "X_1") (pintype "passive"))
      (node (ref "U1") (pin "60") (pinfunction "RF_ANT_60") (pintype "passive"))
    )
    (net (code "34") (name "Net-(Q1-B)") (class "Default")
      (node (ref "Q1") (pin "1") (pinfunction "B_1") (pintype "passive"))
      (node (ref "R10") (pin "1") (pinfunction "1_1") (pintype "passive"))
      (node (ref "R4") (pin "1") (pinfunction "1_1") (pintype "passive"))
    )
    (net (code "35") (name "Net-(Q2-B)") (class "Default")
      (node (ref "Q2") (pin "1") (pinfunction "B_1") (pintype "passive"))
      (node (ref "R11") (pin "1") (pinfunction "1_1") (pintype "passive"))
      (node (ref "R5") (pin "1") (pinfunction "1_1") (pintype "passive"))
    )
    (net (code "36") (name "Net-(Q3-B)") (class "Default")
      (node (ref "Q3") (pin "1") (pinfunction "B_1") (pintype "passive"))
      (node (ref "R13") (pin "1") (pinfunction "1_1") (pintype "passive"))
      (node (ref "R8") (pin "1") (pinfunction "1_1") (pintype "passive"))
    )
    (net (code "37") (name "Net-(Q3-C)") (class "Default")
      (node (ref "Q3") (pin "3") (pinfunction "C_3") (pintype "passive"))
      (node (ref "U1") (pin "1") (pinfunction "PWRKEY_1") (pintype "passive"))
    )
    (net (code "38") (name "Net-(Q4-B)") (class "Default")
      (node (ref "Q4") (pin "1") (pinfunction "B_1") (pintype "passive"))
      (node (ref "R14") (pin "1") (pinfunction "1_1") (pintype "passive"))
      (node (ref "R9") (pin "1") (pinfunction "1_1") (pintype "passive"))
    )
    (net (code "39") (name "Net-(Q4-C)") (class "Default")
      (node (ref "C3") (pin "2") (pinfunction "2_2") (pintype "passive"))
      (node (ref "Q4") (pin "3") (pinfunction "C_3") (pintype "passive"))
      (node (ref "U1") (pin "16") (pinfunction "~{RESET}_16") (pintype "passive"))
    )
    (net (code "40") (name "Net-(Q5-B)") (class "Default")
      (node (ref "Q5") (pin "1") (pinfunction "B_1") (pintype "passive"))
      (node (ref "R23") (pin "1") (pinfunction "1_1") (pintype "passive"))
    )
    (net (code "41") (name "Net-(R19-Pad1)") (class "Default")
      (node (ref "R19") (pin "1") (pinfunction "1_1") (pintype "passive"))
      (node (ref "X2") (pin "1") (pinfunction "1_1") (pintype "passive"))
    )
    (net (code "42") (name "Net-(U1-NETLIGHT)") (class "Default")
      (node (ref "R5") (pin "2") (pinfunction "2_2") (pintype "passive"))
      (node (ref "U1") (pin "52") (pinfunction "NETLIGHT_52") (pintype "passive"))
    )
    (net (code "43") (name "Net-(U1-SIM_CLK)") (class "Default")
      (node (ref "R3") (pin "1") (pinfunction "1_1") (pintype "passive"))
      (node (ref "U1") (pin "32") (pinfunction "SIM_CLK_32") (pintype "passive"))
    )
    (net (code "44") (name "Net-(U1-SIM_DATA)") (class "Default")
      (node (ref "C1") (pin "2") (pinfunction "2_2") (pintype "passive"))
      (node (ref "R1") (pin "1") (pinfunction "1_1") (pintype "passive"))
      (node (ref "R20") (pin "2") (pinfunction "2_2") (pintype "passive"))
      (node (ref "U1") (pin "31") (pinfunction "SIM_DATA_31") (pintype "passive"))
    )
    (net (code "45") (name "Net-(U1-SIM_RST)") (class "Default")
      (node (ref "R2") (pin "1") (pinfunction "1_1") (pintype "passive"))
      (node (ref "U1") (pin "33") (pinfunction "SIM_RST_33") (pintype "passive"))
    )
    (net (code "46") (name "Net-(U1-SIM_VDD)") (class "Default")
      (node (ref "C2") (pin "2") (pinfunction "2_2") (pintype "passive"))
      (node (ref "R20") (pin "1") (pinfunction "1_1") (pintype "passive"))
      (node (ref "U1") (pin "30") (pinfunction "SIM_VDD_30") (pintype "passive"))
      (node (ref "U2") (pin "4") (pinfunction "VCC_4") (pintype "passive"))
      (node (ref "VD1") (pin "1") (pinfunction "1_1") (pintype "passive"))
    )
    (net (code "47") (name "Net-(U1-STATUS)") (class "Default")
      (node (ref "R4") (pin "2") (pinfunction "2_2") (pintype "passive"))
      (node (ref "U1") (pin "66") (pinfunction "STATUS_66") (pintype "passive"))
    )
    (net (code "48") (name "Net-(U1-VRTC)") (class "Default")
      (node (ref "C4") (pin "1") (pinfunction "1_1") (pintype "passive"))
      (node (ref "U1") (pin "26") (pinfunction "VRTC_26") (pintype "passive"))
    )
    (net (code "49") (name "Net-(U2-CLK)") (class "Default")
      (node (ref "R3") (pin "2") (pinfunction "2_2") (pintype "passive"))
      (node (ref "U2") (pin "2") (pinfunction "CLK_2") (pintype "passive"))
      (node (ref "VD1") (pin "6") (pinfunction "6_6") (pintype "passive"))
    )
    (net (code "50") (name "Net-(U2-I{slash}O)") (class "Default")
      (node (ref "R1") (pin "2") (pinfunction "2_2") (pintype "passive"))
      (node (ref "U2") (pin "7") (pinfunction "I/O_7") (pintype "passive"))
      (node (ref "VD1") (pin "3") (pinfunction "3_3") (pintype "passive"))
    )
    (net (code "51") (name "Net-(U2-RST)") (class "Default")
      (node (ref "R2") (pin "2") (pinfunction "2_2") (pintype "passive"))
      (node (ref "U2") (pin "3") (pinfunction "RST_3") (pintype "passive"))
      (node (ref "VD1") (pin "4") (pinfunction "4_4") (pintype "passive"))
    )
    (net (code "52") (name "Net-(U3-PROG)") (class "Default")
      (node (ref "R16") (pin "1") (pinfunction "1_1") (pintype "passive"))
      (node (ref "U3") (pin "5") (pinfunction "PROG_5") (pintype "passive"))
    )
    (net (code "53") (name "Net-(U3-~{CHRG})") (class "Default")
      (node (ref "R12") (pin "1") (pinfunction "1_1") (pintype "passive"))
      (node (ref "U3") (pin "1") (pinfunction "~{CHRG}_1") (pintype "passive"))
    )
    (net (code "54") (name "Net-(U4-FB)") (class "Default")
      (node (ref "R17") (pin "1") (pinfunction "1_1") (pintype "passive"))
      (node (ref "R18") (pin "1") (pinfunction "1_1") (pintype "passive"))
      (node (ref "U4") (pin "4") (pinfunction "FB_4") (pintype "input"))
    )
    (net (code "55") (name "Net-(U5-Out+)") (class "Default")
      (node (ref "C11") (pin "1") (pinfunction "1_1") (pintype "passive"))
      (node (ref "C13") (pin "2") (pinfunction "2_2") (pintype "passive"))
      (node (ref "L1") (pin "2") (pinfunction "2_2") (pintype "passive"))
      (node (ref "R18") (pin "2") (pinfunction "2_2") (pintype "passive"))
      (node (ref "U5") (pin "4") (pinfunction "Out+_4") (pintype "passive"))
      (node (ref "X1") (pin "1") (pinfunction "1_1") (pintype "passive"))
    )
    (net (code "56") (name "Net-(U6-AREF)") (class "Default")
      (node (ref "C16") (pin "2") (pinfunction "2_2") (pintype "passive"))
      (node (ref "U6") (pin "20") (pinfunction "AREF_20") (pintype "passive"))
    )
    (net (code "57") (name "Net-(U6-PB6{slash}XTAL1{slash}TOSC1{slash}PCINT6)") (class "Default")
      (node (ref "C17") (pin "2") (pinfunction "2_2") (pintype "passive"))
      (node (ref "U6") (pin "7") (pinfunction "PB6/XTAL1/TOSC1/PCINT6_7") (pintype "bidirectional"))
      (node (ref "Y1") (pin "1") (pinfunction "OSC1_1") (pintype "passive"))
    )
    (net (code "58") (name "Net-(U6-PB7{slash}XTAL2{slash}TOSC2{slash}PCINT7)") (class "Default")
      (node (ref "C18") (pin "2") (pinfunction "2_2") (pintype "passive"))
      (node (ref "U6") (pin "8") (pinfunction "PB7/XTAL2/TOSC2/PCINT7_8") (pintype "bidirectional"))
      (node (ref "Y1") (pin "2") (pinfunction "OSC2_2") (pintype "passive"))
    )
    (net (code "59") (name "VBAT") (class "Default")
      (node (ref "C15") (pin "2") (pinfunction "2_2") (pintype "passive"))
      (node (ref "C5") (pin "2") (pinfunction "2_2") (pintype "passive"))
      (node (ref "C6") (pin "2") (pinfunction "2_2") (pintype "passive"))
      (node (ref "C7") (pin "2") (pinfunction "2_2") (pintype "passive"))
      (node (ref "C8") (pin "2") (pinfunction "2_2") (pintype "passive"))
      (node (ref "C9") (pin "1") (pinfunction "1_1") (pintype "passive"))
      (node (ref "D1") (pin "2") (pinfunction "K_2") (pintype "passive"))
      (node (ref "D2") (pin "2") (pinfunction "K_2") (pintype "passive"))
      (node (ref "DS1") (pin "1") (pinfunction "A_1") (pintype "passive"))
      (node (ref "DS2") (pin "1") (pinfunction "A_1") (pintype "passive"))
      (node (ref "JP4") (pin "1") (pinfunction "1_1") (pintype "passive"))
      (node (ref "Q5") (pin "2") (pinfunction "E_2") (pintype "passive"))
      (node (ref "U1") (pin "55") (pinfunction "VBAT_55") (pintype "passive"))
      (node (ref "U1") (pin "56") (pinfunction "VBAT_56") (pintype "passive"))
      (node (ref "U1") (pin "57") (pinfunction "VBAT_57") (pintype "passive"))
      (node (ref "U6") (pin "18") (pinfunction "AVCC_18") (pintype "bidirectional"))
      (node (ref "U6") (pin "4") (pinfunction "VCC_4") (pintype "bidirectional"))
      (node (ref "U6") (pin "6") (pinfunction "VCC_6") (pintype "bidirectional"))
    )
    (net (code "60") (name "VDD_EXT") (class "Default")
      (node (ref "R15") (pin "2") (pinfunction "2_2") (pintype "passive"))
      (node (ref "U1") (pin "15") (pinfunction "VDD_EXT_15") (pintype "passive"))
    )
    (net (code "61") (name "unconnected-(U1-ADC-Pad25)") (class "Default")
      (node (ref "U1") (pin "25") (pinfunction "ADC_25") (pintype "passive"))
    )
    (net (code "62") (name "unconnected-(U1-CTS-Pad7)") (class "Default")
      (node (ref "U1") (pin "7") (pinfunction "CTS_7") (pintype "passive"))
    )
    (net (code "63") (name "unconnected-(U1-DBG_RXD-Pad28)") (class "Default")
      (node (ref "U1") (pin "28") (pinfunction "DBG_RXD_28") (pintype "passive"))
    )
    (net (code "64") (name "unconnected-(U1-DBG_TXD-Pad27)") (class "Default")
      (node (ref "U1") (pin "27") (pinfunction "DBG_TXD_27") (pintype "passive"))
    )
    (net (code "65") (name "unconnected-(U1-DCD-Pad5)") (class "Default")
      (node (ref "U1") (pin "5") (pinfunction "DCD_5") (pintype "passive"))
    )
    (net (code "66") (name "unconnected-(U1-DISP_CLK-Pad11)") (class "Default")
      (node (ref "U1") (pin "11") (pinfunction "DISP_CLK_11") (pintype "passive"))
    )
    (net (code "67") (name "unconnected-(U1-DISP_CS-Pad14)") (class "Default")
      (node (ref "U1") (pin "14") (pinfunction "DISP_CS_14") (pintype "passive"))
    )
    (net (code "68") (name "unconnected-(U1-DISP_C{slash}D-Pad13)") (class "Default")
      (node (ref "U1") (pin "13") (pinfunction "DISP_C/D_13") (pintype "passive"))
    )
    (net (code "69") (name "unconnected-(U1-DISP_DATA-Pad12)") (class "Default")
      (node (ref "U1") (pin "12") (pinfunction "DISP_DATA_12") (pintype "passive"))
    )
    (net (code "70") (name "unconnected-(U1-DTR-Pad3)") (class "Default")
      (node (ref "U1") (pin "3") (pinfunction "DTR_3") (pintype "passive"))
    )
    (net (code "71") (name "unconnected-(U1-GPIO1{slash}KBR4-Pad40)") (class "Default")
      (node (ref "U1") (pin "40") (pinfunction "GPIO1/KBR4_40") (pintype "passive"))
    )
    (net (code "72") (name "unconnected-(U1-GPIO2{slash}KBR3-Pad41)") (class "Default")
      (node (ref "U1") (pin "41") (pinfunction "GPIO2/KBR3_41") (pintype "passive"))
    )
    (net (code "73") (name "unconnected-(U1-GPIO3{slash}KBR2-Pad42)") (class "Default")
      (node (ref "U1") (pin "42") (pinfunction "GPIO3/KBR2_42") (pintype "passive"))
    )
    (net (code "74") (name "unconnected-(U1-GPIO4{slash}KPR1-Pad43)") (class "Default")
      (node (ref "U1") (pin "43") (pinfunction "GPIO4/KPR1_43") (pintype "passive"))
    )
    (net (code "75") (name "unconnected-(U1-GPIO5{slash}KBR0-Pad44)") (class "Default")
      (node (ref "U1") (pin "44") (pinfunction "GPIO5/KBR0_44") (pintype "passive"))
    )
    (net (code "76") (name "unconnected-(U1-GPIO6{slash}KBC4-Pad47)") (class "Default")
      (node (ref "U1") (pin "47") (pinfunction "GPIO6/KBC4_47") (pintype "passive"))
    )
    (net (code "77") (name "unconnected-(U1-GPIO7{slash}KBC3-Pad48)") (class "Default")
      (node (ref "U1") (pin "48") (pinfunction "GPIO7/KBC3_48") (pintype "passive"))
    )
    (net (code "78") (name "unconnected-(U1-GPIO8{slash}KBC2-Pad49)") (class "Default")
      (node (ref "U1") (pin "49") (pinfunction "GPIO8/KBC2_49") (pintype "passive"))
    )
    (net (code "79") (name "unconnected-(U1-GPIO9{slash}KBC1-Pad50)") (class "Default")
      (node (ref "U1") (pin "50") (pinfunction "GPIO9/KBC1_50") (pintype "passive"))
    )
    (net (code "80") (name "unconnected-(U1-GPIO10-Pad51)") (class "Default")
      (node (ref "U1") (pin "51") (pinfunction "GPIO10_51") (pintype "passive"))
    )
    (net (code "81") (name "unconnected-(U1-GPIO11-Pad67)") (class "Default")
      (node (ref "U1") (pin "67") (pinfunction "GPIO11_67") (pintype "passive"))
    )
    (net (code "82") (name "unconnected-(U1-GPIO12-Pad68)") (class "Default")
      (node (ref "U1") (pin "68") (pinfunction "GPIO12_68") (pintype "passive"))
    )
    (net (code "83") (name "unconnected-(U1-LINEIN_L-Pad24)") (class "Default")
      (node (ref "U1") (pin "24") (pinfunction "LINEIN_L_24") (pintype "passive"))
    )
    (net (code "84") (name "unconnected-(U1-LINEIN_R-Pad23)") (class "Default")
      (node (ref "U1") (pin "23") (pinfunction "LINEIN_R_23") (pintype "passive"))
    )
    (net (code "85") (name "unconnected-(U1-MIC_N-Pad20)") (class "Default")
      (node (ref "U1") (pin "20") (pinfunction "MIC_N_20") (pintype "passive"))
    )
    (net (code "86") (name "unconnected-(U1-MIC_P-Pad19)") (class "Default")
      (node (ref "U1") (pin "19") (pinfunction "MIC_P_19") (pintype "passive"))
    )
    (net (code "87") (name "unconnected-(U1-NC-Pad2)") (class "Default")
      (node (ref "U1") (pin "2") (pinfunction "NC_2") (pintype "passive"))
    )
    (net (code "88") (name "unconnected-(U1-NC-Pad6)") (class "Default")
      (node (ref "U1") (pin "6") (pinfunction "NC_6") (pintype "passive"))
    )
    (net (code "89") (name "unconnected-(U1-PWM1-Pad35)") (class "Default")
      (node (ref "U1") (pin "35") (pinfunction "PWM1_35") (pintype "passive"))
    )
    (net (code "90") (name "unconnected-(U1-PWM2-Pad36)") (class "Default")
      (node (ref "U1") (pin "36") (pinfunction "PWM2_36") (pintype "passive"))
    )
    (net (code "91") (name "unconnected-(U1-RTS-Pad8)") (class "Default")
      (node (ref "U1") (pin "8") (pinfunction "RTS_8") (pintype "passive"))
    )
    (net (code "92") (name "unconnected-(U1-SCL-Pad38)") (class "Default")
      (node (ref "U1") (pin "38") (pinfunction "SCL_38") (pintype "passive"))
    )
    (net (code "93") (name "unconnected-(U1-SDA-Pad37)") (class "Default")
      (node (ref "U1") (pin "37") (pinfunction "SDA_37") (pintype "passive"))
    )
    (net (code "94") (name "unconnected-(U1-SIM_PRESENCE-Pad34)") (class "Default")
      (node (ref "U1") (pin "34") (pinfunction "SIM_PRESENCE_34") (pintype "passive"))
    )
    (net (code "95") (name "unconnected-(U1-SPK_N-Pad22)") (class "Default")
      (node (ref "U1") (pin "22") (pinfunction "SPK_N_22") (pintype "passive"))
    )
    (net (code "96") (name "unconnected-(U1-SPK_P-Pad21)") (class "Default")
      (node (ref "U1") (pin "21") (pinfunction "SPK_P_21") (pintype "passive"))
    )
    (net (code "97") (name "unconnected-(U2-Pad1)") (class "Default")
      (node (ref "U2") (pin "1") (pintype "passive"))
    )
    (net (code "98") (name "unconnected-(U2-Pad8)") (class "Default")
      (node (ref "U2") (pin "8") (pinfunction "8_8") (pintype "passive"))
    )
    (net (code "99") (name "unconnected-(U2-VPP-Pad6)") (class "Default")
      (node (ref "U2") (pin "6") (pinfunction "VPP_6") (pintype "passive"))
    )
    (net (code "100") (name "unconnected-(U6-PC0{slash}ADC0{slash}PCINT8-Pad23)") (class "Default")
      (node (ref "U6") (pin "23") (pinfunction "PC0/ADC0/PCINT8_23") (pintype "bidirectional"))
    )
    (net (code "101") (name "unconnected-(U6-PC1{slash}ADC1{slash}PCINT9-Pad24)") (class "Default")
      (node (ref "U6") (pin "24") (pinfunction "PC1/ADC1/PCINT9_24") (pintype "bidirectional"))
    )
    (net (code "102") (name "unconnected-(U6-PC2{slash}ADC2{slash}PCINT10-Pad25)") (class "Default")
      (node (ref "U6") (pin "25") (pinfunction "PC2/ADC2/PCINT10_25") (pintype "bidirectional"))
    )
    (net (code "103") (name "unconnected-(U6-PC3{slash}ADC3{slash}PCINT10-Pad26)") (class "Default")
      (node (ref "U6") (pin "26") (pinfunction "PC3/ADC3/PCINT10_26") (pintype "bidirectional"))
    )
    (net (code "104") (name "unconnected-(VD1-Pad5)") (class "Default")
      (node (ref "VD1") (pin "5") (pinfunction "5_5") (pintype "passive"))
    )
  )
)
